# dispay.net
KiCad netlist of a schematic drawn in Altium Designer
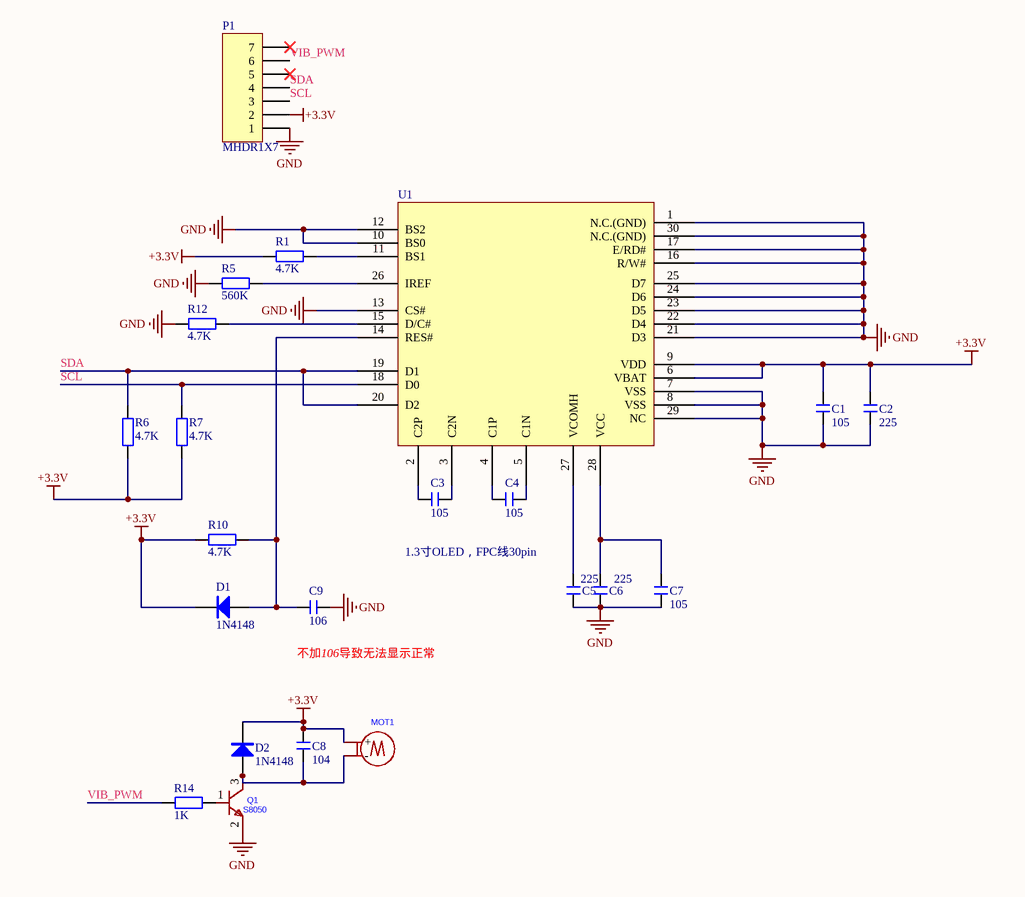
[diagram p0: dispay.SchDoc]

(export (version "E")
  (design (tool "Eeschema 10.0.6"))
  (components
    (comp (ref "C1")
      (value "105")
      (footprint "C0402-min")
      (description "无极性贴片电容")
      (fields (field (name "版权归属") "源创客"))
      (libsource (lib "3.1   - 电阻-电容-电感") (part "C"))
    )
    (comp (ref "C2")
      (value "225")
      (footprint "C0402-min")
      (description "无极性贴片电容")
      (fields (field (name "版权归属") "源创客"))
      (libsource (lib "3.1   - 电阻-电容-电感") (part "C"))
    )
    (comp (ref "C3")
      (value "105")
      (footprint "C0402-min")
      (description "无极性贴片电容")
      (fields (field (name "版权归属") "源创客"))
      (libsource (lib "3.1   - 电阻-电容-电感") (part "C"))
    )
    (comp (ref "C4")
      (value "105")
      (footprint "C0402-min")
      (description "无极性贴片电容")
      (fields (field (name "版权归属") "源创客"))
      (libsource (lib "3.1   - 电阻-电容-电感") (part "C"))
    )
    (comp (ref "C5")
      (value "225")
      (footprint "C0402-min")
      (description "无极性贴片电容")
      (fields (field (name "版权归属") "源创客"))
      (libsource (lib "3.1   - 电阻-电容-电感") (part "C"))
    )
    (comp (ref "C6")
      (value "225")
      (footprint "C0402-min")
      (description "无极性贴片电容")
      (fields (field (name "版权归属") "源创客"))
      (libsource (lib "3.1   - 电阻-电容-电感") (part "C"))
    )
    (comp (ref "C7")
      (value "105")
      (footprint "C0402-min")
      (description "无极性贴片电容")
      (fields (field (name "版权归属") "源创客"))
      (libsource (lib "3.1   - 电阻-电容-电感") (part "C"))
    )
    (comp (ref "C8")
      (value "104")
      (footprint "C0402-min")
      (description "无极性贴片电容")
      (fields (field (name "版权归属") "源创客"))
      (libsource (lib "3.1   - 电阻-电容-电感") (part "C"))
    )
    (comp (ref "C9")
      (value "106")
      (footprint "C0402-min")
      (description "无极性贴片电容")
      (fields (field (name "版权归属") "源创客"))
      (libsource (lib "3.1   - 电阻-电容-电感") (part "C"))
    )
    (comp (ref "D1")
      (value "1N4148")
      (footprint "SOD-323")
      (description "高速开关二极管")
      (fields (field (name "版权归属") "源创客"))
      (libsource (lib "8.1   - 二极管-整流桥") (part "1N4148"))
    )
    (comp (ref "D2")
      (value "1N4148")
      (footprint "SOD-323")
      (description "高速开关二极管")
      (fields (field (name "版权归属") "源创客"))
      (libsource (lib "8.1   - 二极管-整流桥") (part "1N4148"))
    )
    (comp (ref "MOT1")
      (value "LCM1027A2445F")
      (footprint "Vibration_Motor0820")
      (fields (field (name "MANUFACTURER") "LEADER(立得)"))
      (libsource (lib "drive") (part "Vibration_Motor"))
    )
    (comp (ref "P1")
      (value "MHDR1X7")
      (footprint "MHDR1X7")
      (description "Header, 7-Pin")
      (fields (field (name "PUBLISHER") "Altium Limited"))
      (libsource (lib "Miscellaneous Connectors") (part "MHDR1X7"))
    )
    (comp (ref "Q1")
      (value "S8050")
      (footprint "SOT-23-3")
      (fields (field (name "MANUFACTURER") "宏嘉诚"))
      (libsource (lib "drive") (part "S8050"))
    )
    (comp (ref "R1")
      (value "4.7K")
      (footprint "R0402")
      (description "贴片电阻")
      (fields (field (name "版权归属") "源创客"))
      (libsource (lib "3.1   - 电阻-电容-电感") (part "R"))
    )
    (comp (ref "R5")
      (value "560K")
      (footprint "R0402")
      (description "贴片电阻")
      (fields (field (name "版权归属") "源创客"))
      (libsource (lib "3.1   - 电阻-电容-电感") (part "R"))
    )
    (comp (ref "R6")
      (value "4.7K")
      (footprint "R0402")
      (description "贴片电阻")
      (fields (field (name "版权归属") "源创客"))
      (libsource (lib "3.1   - 电阻-电容-电感") (part "R"))
    )
    (comp (ref "R7")
      (value "4.7K")
      (footprint "R0402")
      (description "贴片电阻")
      (fields (field (name "版权归属") "源创客"))
      (libsource (lib "3.1   - 电阻-电容-电感") (part "R"))
    )
    (comp (ref "R10")
      (value "4.7K")
      (footprint "R0402")
      (description "贴片电阻")
      (fields (field (name "版权归属") "源创客"))
      (libsource (lib "3.1   - 电阻-电容-电感") (part "R"))
    )
    (comp (ref "R12")
      (value "4.7K")
      (footprint "R0402")
      (description "贴片电阻")
      (fields (field (name "版权归属") "源创客"))
      (libsource (lib "3.1   - 电阻-电容-电感") (part "R"))
    )
    (comp (ref "R14")
      (value "1K")
      (footprint "R0402")
      (description "贴片电阻")
      (fields (field (name "版权归属") "源创客"))
      (libsource (lib "3.1   - 电阻-电容-电感") (part "R"))
    )
    (comp (ref "U1")
      (value "1.3寸OLED，FPC线30pin")
      (footprint "0.96OLED")
      (libsource (lib "我的元件") (part "1.3寸OLED，FPC线30pin"))
    )
  )
  (nets
    (net (code "1") (name "+3.3V") (class "Default")
      (node (ref "C1") (pin "2") (pinfunction "2_2") (pintype "passive"))
      (node (ref "C2") (pin "2") (pinfunction "2_2") (pintype "passive"))
      (node (ref "C8") (pin "2") (pinfunction "2_2") (pintype "passive"))
      (node (ref "D1") (pin "2") (pinfunction "K_2") (pintype "passive"))
      (node (ref "D2") (pin "2") (pinfunction "K_2") (pintype "passive"))
      (node (ref "MOT1") (pin "2") (pinfunction "+_2") (pintype "passive"))
      (node (ref "P1") (pin "2") (pinfunction "2_2") (pintype "passive"))
      (node (ref "R1") (pin "1") (pinfunction "1_1") (pintype "passive"))
      (node (ref "R10") (pin "1") (pinfunction "1_1") (pintype "passive"))
      (node (ref "R6") (pin "1") (pinfunction "1_1") (pintype "passive"))
      (node (ref "R7") (pin "1") (pinfunction "1_1") (pintype "passive"))
      (node (ref "U1") (pin "6") (pinfunction "VBAT_6") (pintype "passive"))
      (node (ref "U1") (pin "9") (pinfunction "VDD_9") (pintype "passive"))
    )
    (net (code "2") (name "/SCL") (class "Default")
      (node (ref "P1") (pin "3") (pinfunction "3_3") (pintype "passive"))
      (node (ref "R7") (pin "2") (pinfunction "2_2") (pintype "passive"))
      (node (ref "U1") (pin "18") (pinfunction "D0_18") (pintype "passive"))
    )
    (net (code "3") (name "/SDA") (class "Default")
      (node (ref "P1") (pin "4") (pinfunction "4_4") (pintype "passive"))
      (node (ref "R6") (pin "2") (pinfunction "2_2") (pintype "passive"))
      (node (ref "U1") (pin "19") (pinfunction "D1_19") (pintype "passive"))
      (node (ref "U1") (pin "20") (pinfunction "D2_20") (pintype "passive"))
    )
    (net (code "4") (name "/VIB_PWM") (class "Default")
      (node (ref "P1") (pin "6") (pinfunction "6_6") (pintype "passive"))
      (node (ref "R14") (pin "1") (pinfunction "1_1") (pintype "passive"))
    )
    (net (code "5") (name "GND") (class "Default")
      (node (ref "C1") (pin "1") (pinfunction "1_1") (pintype "passive"))
      (node (ref "C2") (pin "1") (pinfunction "1_1") (pintype "passive"))
      (node (ref "C5") (pin "1") (pinfunction "1_1") (pintype "passive"))
      (node (ref "C6") (pin "1") (pinfunction "1_1") (pintype "passive"))
      (node (ref "C7") (pin "1") (pinfunction "1_1") (pintype "passive"))
      (node (ref "C9") (pin "2") (pinfunction "2_2") (pintype "passive"))
      (node (ref "P1") (pin "1") (pinfunction "1_1") (pintype "passive"))
      (node (ref "Q1") (pin "2") (pinfunction "E_2") (pintype "passive"))
      (node (ref "R12") (pin "2") (pinfunction "2_2") (pintype "passive"))
      (node (ref "R5") (pin "1") (pinfunction "1_1") (pintype "passive"))
      (node (ref "U1") (pin "1") (pinfunction "N.C.(GND)_1") (pintype "passive"))
      (node (ref "U1") (pin "10") (pinfunction "BS0_10") (pintype "passive"))
      (node (ref "U1") (pin "12") (pinfunction "BS2_12") (pintype "passive"))
      (node (ref "U1") (pin "13") (pinfunction "CS#_13") (pintype "passive"))
      (node (ref "U1") (pin "16") (pinfunction "R/W#_16") (pintype "passive"))
      (node (ref "U1") (pin "17") (pinfunction "E/RD#_17") (pintype "passive"))
      (node (ref "U1") (pin "21") (pinfunction "D3_21") (pintype "passive"))
      (node (ref "U1") (pin "22") (pinfunction "D4_22") (pintype "passive"))
      (node (ref "U1") (pin "23") (pinfunction "D5_23") (pintype "passive"))
      (node (ref "U1") (pin "24") (pinfunction "D6_24") (pintype "passive"))
      (node (ref "U1") (pin "25") (pinfunction "D7_25") (pintype "passive"))
      (node (ref "U1") (pin "29") (pinfunction "NC_29") (pintype "passive"))
      (node (ref "U1") (pin "30") (pinfunction "N.C.(GND)_30") (pintype "passive"))
      (node (ref "U1") (pin "7") (pinfunction "VSS_7") (pintype "passive"))
      (node (ref "U1") (pin "8") (pinfunction "VSS_8") (pintype "passive"))
    )
    (net (code "6") (name "Net-(D1-A)") (class "Default")
      (node (ref "C9") (pin "1") (pinfunction "1_1") (pintype "passive"))
      (node (ref "D1") (pin "1") (pinfunction "A_1") (pintype "passive"))
      (node (ref "R10") (pin "2") (pinfunction "2_2") (pintype "passive"))
      (node (ref "U1") (pin "14") (pinfunction "RES#_14") (pintype "passive"))
    )
    (net (code "7") (name "Net-(D2-A)") (class "Default")
      (node (ref "C8") (pin "1") (pinfunction "1_1") (pintype "passive"))
      (node (ref "D2") (pin "1") (pinfunction "A_1") (pintype "passive"))
      (node (ref "MOT1") (pin "1") (pinfunction "-_1") (pintype "passive"))
      (node (ref "Q1") (pin "3") (pinfunction "C_3") (pintype "passive"))
    )
    (net (code "8") (name "Net-(Q1-B)") (class "Default")
      (node (ref "Q1") (pin "1") (pinfunction "B_1") (pintype "passive"))
      (node (ref "R14") (pin "2") (pinfunction "2_2") (pintype "passive"))
    )
    (net (code "9") (name "Net-(U1-BS1)") (class "Default")
      (node (ref "R1") (pin "2") (pinfunction "2_2") (pintype "passive"))
      (node (ref "U1") (pin "11") (pinfunction "BS1_11") (pintype "passive"))
    )
    (net (code "10") (name "Net-(U1-C1N)") (class "Default")
      (node (ref "C4") (pin "2") (pinfunction "2_2") (pintype "passive"))
      (node (ref "U1") (pin "5") (pinfunction "C1N_5") (pintype "passive"))
    )
    (net (code "11") (name "Net-(U1-C1P)") (class "Default")
      (node (ref "C4") (pin "1") (pinfunction "1_1") (pintype "passive"))
      (node (ref "U1") (pin "4") (pinfunction "C1P_4") (pintype "passive"))
    )
    (net (code "12") (name "Net-(U1-C2N)") (class "Default")
      (node (ref "C3") (pin "2") (pinfunction "2_2") (pintype "passive"))
      (node (ref "U1") (pin "3") (pinfunction "C2N_3") (pintype "passive"))
    )
    (net (code "13") (name "Net-(U1-C2P)") (class "Default")
      (node (ref "C3") (pin "1") (pinfunction "1_1") (pintype "passive"))
      (node (ref "U1") (pin "2") (pinfunction "C2P_2") (pintype "passive"))
    )
    (net (code "14") (name "Net-(U1-D{slash}C#)") (class "Default")
      (node (ref "R12") (pin "1") (pinfunction "1_1") (pintype "passive"))
      (node (ref "U1") (pin "15") (pinfunction "D/C#_15") (pintype "passive"))
    )
    (net (code "15") (name "Net-(U1-IREF)") (class "Default")
      (node (ref "R5") (pin "2") (pinfunction "2_2") (pintype "passive"))
      (node (ref "U1") (pin "26") (pinfunction "IREF_26") (pintype "passive"))
    )
    (net (code "16") (name "Net-(U1-VCC)") (class "Default")
      (node (ref "C6") (pin "2") (pinfunction "2_2") (pintype "passive"))
      (node (ref "C7") (pin "2") (pinfunction "2_2") (pintype "passive"))
      (node (ref "U1") (pin "28") (pinfunction "VCC_28") (pintype "passive"))
    )
    (net (code "17") (name "Net-(U1-VCOMH)") (class "Default")
      (node (ref "C5") (pin "2") (pinfunction "2_2") (pintype "passive"))
      (node (ref "U1") (pin "27") (pinfunction "VCOMH_27") (pintype "passive"))
    )
    (net (code "18") (name "unconnected-(P1-Pad5)") (class "Default")
      (node (ref "P1") (pin "5") (pinfunction "5_5") (pintype "passive+no_connect"))
    )
    (net (code "19") (name "unconnected-(P1-Pad7)") (class "Default")
      (node (ref "P1") (pin "7") (pinfunction "7_7") (pintype "passive+no_connect"))
    )
  )
)
